# HPF.net
KiCad netlist of a schematic drawn in Altium Designer
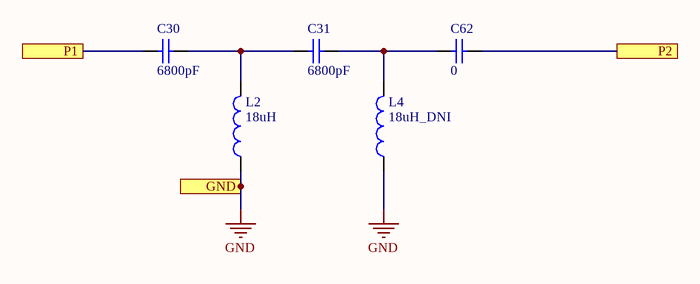
[diagram p0: HPF.SchDoc]

(export (version "E")
  (design (tool "Eeschema 10.0.6"))
  (components
    (comp (ref "C30")
      (value "6800pF")
      (footprint "SMD-0603")
      (description "Ceramic Capacitor 0603")
      (libsource (lib "LCR") (part "CAP0603"))
    )
    (comp (ref "C31")
      (value "6800pF")
      (footprint "SMD-0603")
      (description "Ceramic Capacitor 0603")
      (libsource (lib "LCR") (part "CAP0603"))
    )
    (comp (ref "C62")
      (value "0")
      (footprint "SMD-0603")
      (description "Ceramic Capacitor 0603")
      (libsource (lib "LCR") (part "CAP0603"))
    )
    (comp (ref "L2")
      (value "18uH")
      (footprint "SMD-0603")
      (description "Inductor 0603")
      (libsource (lib "LCR") (part "L0603"))
    )
    (comp (ref "L4")
      (value "18uH_DNI")
      (footprint "SMD-0603")
      (description "Inductor 0603")
      (libsource (lib "LCR") (part "L0603"))
    )
  )
  (nets
    (net (code "1") (name "/P1") (class "Default")
      (node (ref "C30") (pin "1") (pinfunction "1_1") (pintype "passive"))
    )
    (net (code "2") (name "/P2") (class "Default")
      (node (ref "C62") (pin "2") (pinfunction "2_2") (pintype "passive"))
    )
    (net (code "3") (name "GND") (class "Default")
      (node (ref "L2") (pin "1") (pinfunction "1_1") (pintype "passive"))
      (node (ref "L4") (pin "1") (pinfunction "1_1") (pintype "passive"))
    )
    (net (code "4") (name "Net-(C30-Pad2)") (class "Default")
      (node (ref "C30") (pin "2") (pinfunction "2_2") (pintype "passive"))
      (node (ref "C31") (pin "1") (pinfunction "1_1") (pintype "passive"))
      (node (ref "L2") (pin "2") (pinfunction "2_2") (pintype "passive"))
    )
    (net (code "5") (name "Net-(C31-Pad2)") (class "Default")
      (node (ref "C31") (pin "2") (pinfunction "2_2") (pintype "passive"))
      (node (ref "C62") (pin "1") (pinfunction "1_1") (pintype "passive"))
      (node (ref "L4") (pin "2") (pinfunction "2_2") (pintype "passive"))
    )
  )
)
